# Charging.net
KiCad netlist of a schematic drawn in Altium Designer
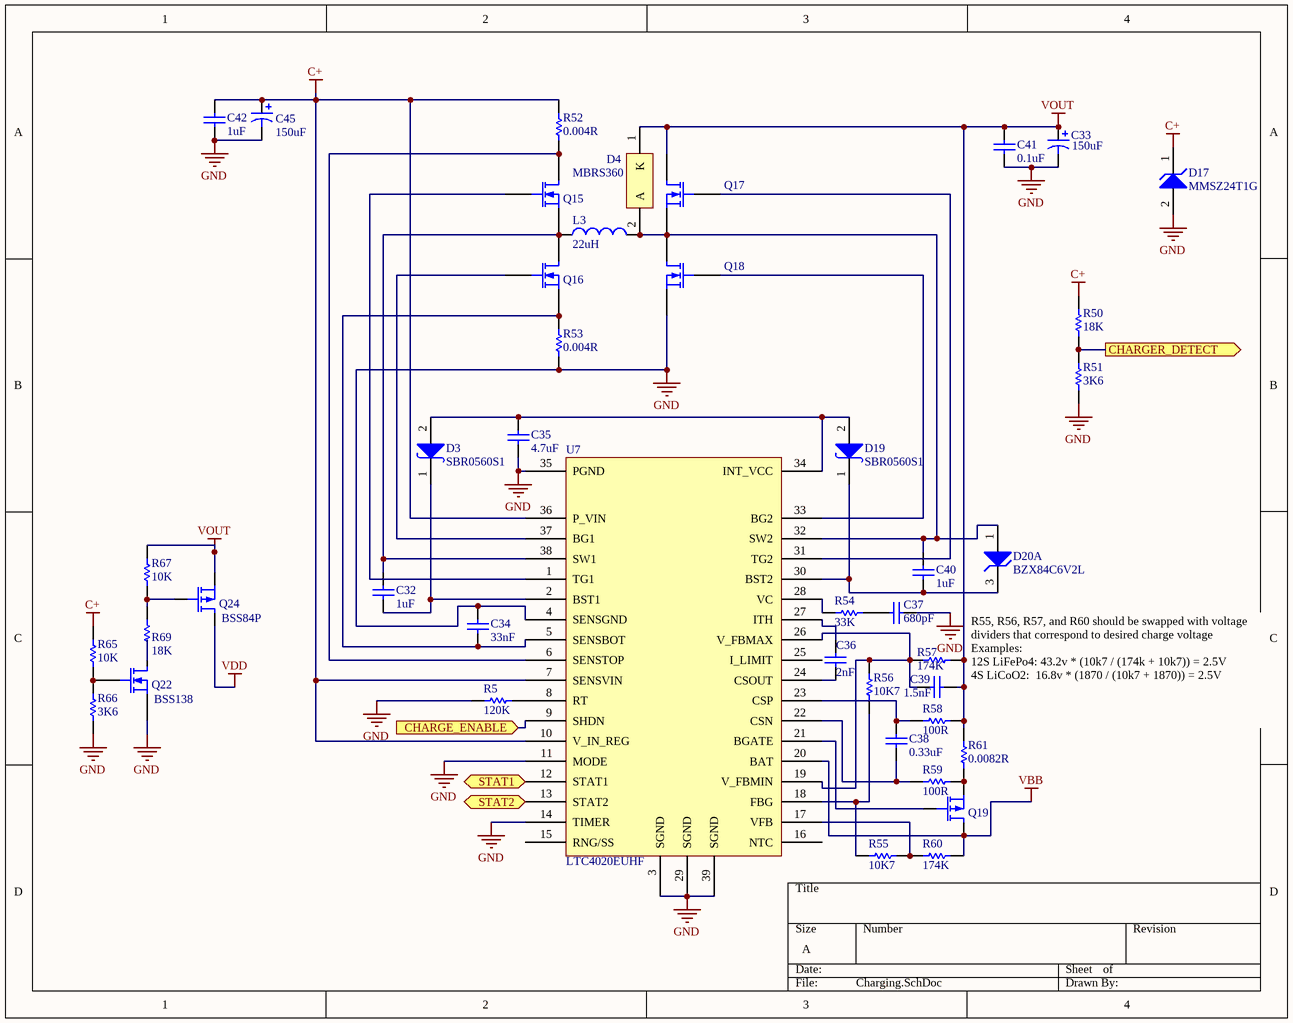
[diagram p0: Charging.SchDoc]

(export (version "E")
  (design (tool "Eeschema 10.0.6"))
  (components
    (comp (ref "C32")
      (value "1uF")
      (footprint "CAPC0603(1608)100_L")
      (description "CAP 1uF 25V Â±10% 0603 (1608 Metric) Thickness 1mm SMD")
      (fields (field (name "TOLERANCE") "Â±10%"))
      (libsource (lib "Altium Content Vault") (part "CAP"))
    )
    (comp (ref "C33")
      (value "150uF")
      (footprint "CAP 180uF 50V")
      (description "Polarized Capacitor (Axial)")
      (fields (field (name "PUBLISHER") "Altium Limited"))
      (libsource (lib "Components") (part "CAP 180uF 50V"))
    )
    (comp (ref "C34")
      (value "33nF")
      (footprint "CAPC0603(1608)100_L")
      (description "CAP 33nF 25V Â±5% 0603 (1608 Metric) Thickness 1mm SMD")
      (fields (field (name "TOLERANCE") "Â±5%"))
      (libsource (lib "Altium Content Vault") (part "CMP-1035-02463-1"))
    )
    (comp (ref "C35")
      (value "4.7uF")
      (footprint "CAPC0603(1608)55_L")
      (description "CAP 4.7uF 6.3V Â±10% 0603 (1608 Metric) Thickness 0.55mm SMD")
      (fields (field (name "TOLERANCE") "Â±10%"))
      (libsource (lib "Altium Content Vault") (part "CMP-1035-02779-1"))
    )
    (comp (ref "C36")
      (value "2nF")
      (footprint "CAPC0603(1608)100_L")
      (description "CAP 2.2nF 6.3V Â±5% 0603 (1608 Metric) Thickness 1mm SMD")
      (fields (field (name "TOLERANCE") "Â±5%"))
      (libsource (lib "Altium Content Vault") (part "CAP"))
    )
    (comp (ref "C37")
      (value "680pF")
      (footprint "CAPC0603(1608)100_L")
      (description "CAP 680pF 6.3V Â±5% 0603 (1608 Metric) Thickness 1mm SMD")
      (fields (field (name "TOLERANCE") "Â±5%"))
      (libsource (lib "Altium Content Vault") (part "CAP"))
    )
    (comp (ref "C38")
      (value "0.33uF")
      (footprint "CAPC0603(1608)100_L")
      (description "CAP 330nF 50V Â±10% 0603 (1608 Metric) Thickness 1mm SMD")
      (fields (field (name "TOLERANCE") "Â±10%"))
      (libsource (lib "Altium Content Vault") (part "CMP-1035-02679-1"))
    )
    (comp (ref "C39")
      (value "1.5nF")
      (footprint "CAPC0603(1608)100_N")
      (description "CAP 1.5nF 6.3V Â±5% 0603 (1608 Metric) Thickness 1mm SMD")
      (fields (field (name "TOLERANCE") "Â±5%"))
      (libsource (lib "Altium Content Vault") (part "CAP"))
    )
    (comp (ref "C40")
      (value "1uF")
      (footprint "CAPC0603(1608)100_L")
      (description "CAP 1uF 25V Â±10% 0603 (1608 Metric) Thickness 1mm SMD")
      (fields (field (name "TOLERANCE") "Â±10%"))
      (libsource (lib "Altium Content Vault") (part "CAP"))
    )
    (comp (ref "C41")
      (value "0.1uF")
      (footprint "CAPC0603(1608)100_L")
      (description "CAP 100nF 50V Â±5% 0603 (1608 Metric) Thickness 1mm SMD")
      (fields (field (name "TOLERANCE") "Â±5%"))
      (libsource (lib "Altium Content Vault") (part "CMP-1035-02591-1"))
    )
    (comp (ref "C42")
      (value "1uF")
      (footprint "CAPC0603(1608)100_L")
      (description "CAP 1uF 25V Â±10% 0603 (1608 Metric) Thickness 1mm SMD")
      (fields (field (name "TOLERANCE") "Â±10%"))
      (libsource (lib "Altium Content Vault") (part "CAP"))
    )
    (comp (ref "C45")
      (value "150uF")
      (footprint "CAP 150uF 25V")
      (description "Polarized Capacitor (Axial)")
      (fields (field (name "PUBLISHER") "Altium Limited"))
      (libsource (lib "Components") (part "CAP 150uF 25V"))
    )
    (comp (ref "D3")
      (value "SBR0560S1")
      (footprint "SOD-123")
      (libsource (lib "Components") (part "SBR0560S1"))
    )
    (comp (ref "D4")
      (value "MBRS360")
      (footprint "ONSC-SMB-2-403A-03_H_V")
      (description "Schottky Power Rectifier, 2-Pin SMB, Pb-Free, Tape and Reel")
      (fields (field (name "MANUFACTURER") "On Semiconductor") (field (name "PARTNUMBER") "MBRS360BT3G"))
      (libsource (lib "Altium Content Vault") (part "ONSC-D-K1A2-2_A"))
    )
    (comp (ref "D17")
      (value "MMSZ24T1G")
      (footprint "ONSC-SOD-123-2-425-04_V")
      (description "Zener Voltage Regulator, 500 mW, 2-Pin SOD-123, Pb-Free, Tape and Reel")
      (fields (field (name "MANUFACTURER") "On Semiconductor"))
      (libsource (lib "Altium Content Vault") (part "CMP-1060-00237-1"))
    )
    (comp (ref "D19")
      (value "SBR0560S1")
      (footprint "SOD-123")
      (libsource (lib "Components") (part "SBR0560S1"))
    )
    (comp (ref "D20")
      (value "BZX84C6V2L")
      (footprint "ONSC-SOT-23-3-318-08_V")
      (description "Zener Voltage Regulator, 225 mW, 3-Pin SOT-23, Pb-Free, Tape and Reel")
      (fields (field (name "MANUFACTURER") "On Semiconductor") (field (name "PARTNUMBER") "BZX84C6V2LT3G"))
      (libsource (lib "Altium Content Vault") (part "CMP-1060-00911-1"))
    )
    (comp (ref "L3")
      (value "22uH")
      (footprint "IHLP-6767GZ")
      (description "Inductor")
      (fields (field (name "PUBLISHER") "Altium Limited"))
      (libsource (lib "Components") (part "IHLP6767"))
    )
    (comp (ref "Q15")
      (value "FDS5672")
      (footprint "SOIC127P600X175-8N")
      (description "N-Channel MOSFET")
      (fields (field (name "PUBLISHER") "Altium Limited"))
      (libsource (lib "Components") (part "MOSFET-N"))
    )
    (comp (ref "Q16")
      (value "FDS5672")
      (footprint "SOIC127P600X175-8N")
      (description "N-Channel MOSFET")
      (fields (field (name "PUBLISHER") "Altium Limited"))
      (libsource (lib "Components") (part "MOSFET-N"))
    )
    (comp (ref "Q17")
      (value "FDS5672")
      (footprint "SOIC127P600X175-8N")
      (description "N-Channel MOSFET")
      (fields (field (name "PUBLISHER") "Altium Limited"))
      (libsource (lib "Components") (part "MOSFET-N"))
    )
    (comp (ref "Q18")
      (value "FDS5672")
      (footprint "SOIC127P600X175-8N")
      (description "N-Channel MOSFET")
      (fields (field (name "PUBLISHER") "Altium Limited"))
      (libsource (lib "Components") (part "MOSFET-N"))
    )
    (comp (ref "Q19")
      (value "SQJ461EP-T1")
      (footprint "SOIC127P600X175-8N")
      (description "P-Channel MOSFET")
      (fields (field (name "PUBLISHER") "Altium Limited"))
      (libsource (lib "Components") (part "MOSFET-P"))
    )
    (comp (ref "Q22")
      (value "BSS138")
      (footprint "SOT23-3")
      (description "N-Channel MOSFET")
      (fields (field (name "PUBLISHER") "Altium Limited"))
      (libsource (lib "Components") (part "MOSFET-N"))
    )
    (comp (ref "Q24")
      (value "BSS84P")
      (footprint "SOT23-3")
      (description "P-Channel MOSFET")
      (fields (field (name "MODEL") "BSS84P") (field (name "PUBLISHER") "Altium Limited"))
      (libsource (lib "Components") (part "MOSFET-P"))
    )
    (comp (ref "R5")
      (value "120K")
      (footprint "RESC0603(1608)_L")
      (description "120K 0.1W 5% 0603 (1608 Metric)  SMD")
      (fields (field (name "POWER") "0.1 W") (field (name "TOLERANCE") "5 %"))
      (libsource (lib "Altium Content Vault") (part "CMP-1012-00124-1"))
    )
    (comp (ref "R50")
      (value "18K")
      (footprint "RESC0603(1608)_L")
      (description "18K 0.1W 1% 0603 (1608 Metric)  SMD")
      (fields (field (name "POWER") "0.1 W") (field (name "TOLERANCE") "1 %"))
      (libsource (lib "Altium Content Vault") (part "CMP-1012-00650-1"))
    )
    (comp (ref "R51")
      (value "3K6")
      (footprint "RESC0603(1608)_L")
      (description "3K6 0.1W 1% 0603 (1608 Metric)  SMD")
      (fields (field (name "TOLERANCE") "1 %") (field (name "POWER") "0.1 W"))
      (libsource (lib "Altium Content Vault") (part "RES"))
    )
    (comp (ref "R52")
      (value "0.004R")
      (footprint "RESC1206(3216)_L")
      (description "1R 0.25W 1% 1206 (3216 Metric)  SMD")
      (fields (field (name "POWER") "0.25 W") (field (name "TOLERANCE") "1 %"))
      (libsource (lib "Altium Content Vault") (part "RES"))
    )
    (comp (ref "R53")
      (value "0.004R")
      (footprint "RESC1206(3216)_L")
      (description "1R 0.25W 1% 1206 (3216 Metric)  SMD")
      (fields (field (name "POWER") "0.25 W") (field (name "TOLERANCE") "1 %"))
      (libsource (lib "Altium Content Vault") (part "RES"))
    )
    (comp (ref "R54")
      (value "33K")
      (footprint "RESC0603(1608)_N")
      (description "33K 0.1W 1% 0603 (1608 Metric)  SMD")
      (fields (field (name "TOLERANCE") "1 %") (field (name "POWER") "0.1 W"))
      (libsource (lib "Altium Content Vault") (part "RES"))
    )
    (comp (ref "R55")
      (value "10K7")
      (footprint "RESC0603(1608)_L")
      (description "110K 0.1W 5% 0603 (1608 Metric)  SMD")
      (fields (field (name "TOLERANCE") "5 %") (field (name "POWER") "0.1 W"))
      (libsource (lib "Altium Content Vault") (part "CMP-1012-00123-1"))
    )
    (comp (ref "R56")
      (value "10K7")
      (footprint "RESC0603(1608)_L")
      (description "110K 0.1W 5% 0603 (1608 Metric)  SMD")
      (fields (field (name "TOLERANCE") "5 %") (field (name "POWER") "0.1 W"))
      (libsource (lib "Altium Content Vault") (part "CMP-1012-00123-1"))
    )
    (comp (ref "R57")
      (value "174K")
      (footprint "RESC0603(1608)_L")
      (description "1M8 0.1W 5% 0603 (1608 Metric)  SMD")
      (fields (field (name "TOLERANCE") "5 %") (field (name "POWER") "0.1 W"))
      (libsource (lib "Altium Content Vault") (part "RES"))
    )
    (comp (ref "R58")
      (value "100R")
      (footprint "RESC0603(1608)_L")
      (description "100R 0.1W 5% 0603 (1608 Metric)  SMD")
      (fields (field (name "TOLERANCE") "5 %") (field (name "POWER") "0.1 W"))
      (libsource (lib "Altium Content Vault") (part "RES"))
    )
    (comp (ref "R59")
      (value "100R")
      (footprint "RESC0603(1608)_L")
      (description "100R 0.1W 5% 0603 (1608 Metric)  SMD")
      (fields (field (name "TOLERANCE") "5 %") (field (name "POWER") "0.1 W"))
      (libsource (lib "Altium Content Vault") (part "RES"))
    )
    (comp (ref "R60")
      (value "174K")
      (footprint "RESC0603(1608)_L")
      (description "1M8 0.1W 5% 0603 (1608 Metric)  SMD")
      (fields (field (name "TOLERANCE") "5 %") (field (name "POWER") "0.1 W"))
      (libsource (lib "Altium Content Vault") (part "CMP-1012-00152-1"))
    )
    (comp (ref "R61")
      (value "0.0082R")
      (footprint "RESC2010(5025)_M")
      (description "1R 0.75W 1% 2010 (5025 Metric)  SMD")
      (fields (field (name "TOLERANCE") "1 %") (field (name "POWER") "0.75 W"))
      (libsource (lib "Altium Content Vault") (part "CMP-1017-00171-1"))
    )
    (comp (ref "R65")
      (value "10K")
      (footprint "RESC0603(1608)_N")
      (description "10K 0.1W 5% 0603 (1608 Metric)  SMD")
      (fields (field (name "TOLERANCE") "5 %") (field (name "POWER") "0.1 W"))
      (libsource (lib "Altium Content Vault") (part "RES"))
    )
    (comp (ref "R66")
      (value "3K6")
      (footprint "RESC0603(1608)_N")
      (description "3K6 0.1W 5% 0603 (1608 Metric)  SMD")
      (fields (field (name "POWER") "0.1 W") (field (name "TOLERANCE") "5 %"))
      (libsource (lib "Altium Content Vault") (part "RES"))
    )
    (comp (ref "R67")
      (value "10K")
      (footprint "RESC0603(1608)_N")
      (description "10K 0.1W 5% 0603 (1608 Metric)  SMD")
      (fields (field (name "TOLERANCE") "5 %") (field (name "POWER") "0.1 W"))
      (libsource (lib "Altium Content Vault") (part "RES"))
    )
    (comp (ref "R69")
      (value "18K")
      (footprint "RESC0603(1608)_N")
      (description "18K 0.1W 5% 0603 (1608 Metric)  SMD")
      (fields (field (name "TOLERANCE") "5 %") (field (name "POWER") "0.1 W"))
      (libsource (lib "Altium Content Vault") (part "RES"))
    )
    (comp (ref "U7")
      (value "LTC4020EUHF")
      (footprint "QFN38")
      (libsource (lib "Components") (part "LTC4020EUHF"))
    )
  )
  (nets
    (net (code "1") (name "/CHARGER_DETECT") (class "Default")
      (node (ref "R50") (pin "1") (pinfunction "1_1") (pintype "passive"))
      (node (ref "R51") (pin "2") (pinfunction "2_2") (pintype "passive"))
    )
    (net (code "2") (name "/CHARGE_ENABLE") (class "Default")
      (node (ref "U7") (pin "9") (pinfunction "SHDN_9") (pintype "passive"))
    )
    (net (code "3") (name "/STAT1") (class "Default")
      (node (ref "U7") (pin "12") (pinfunction "STAT1_12") (pintype "passive"))
    )
    (net (code "4") (name "/STAT2") (class "Default")
      (node (ref "U7") (pin "13") (pinfunction "STAT2_13") (pintype "passive"))
    )
    (net (code "5") (name "C+") (class "Default")
      (node (ref "C42") (pin "2") (pinfunction "2_2") (pintype "passive"))
      (node (ref "C45") (pin "1") (pinfunction "1_1") (pintype "passive"))
      (node (ref "D17") (pin "1") (pinfunction "K_1") (pintype "passive"))
      (node (ref "R50") (pin "2") (pinfunction "2_2") (pintype "passive"))
      (node (ref "R52") (pin "2") (pinfunction "2_2") (pintype "passive"))
      (node (ref "R65") (pin "2") (pinfunction "2_2") (pintype "passive"))
      (node (ref "U7") (pin "10") (pinfunction "V_IN_REG_10") (pintype "passive"))
      (node (ref "U7") (pin "36") (pinfunction "P_VIN_36") (pintype "passive"))
      (node (ref "U7") (pin "7") (pinfunction "SENSVIN_7") (pintype "passive"))
    )
    (net (code "6") (name "GND") (class "Default")
      (node (ref "C33") (pin "2") (pinfunction "2_2") (pintype "passive"))
      (node (ref "C34") (pin "2") (pinfunction "2_2") (pintype "passive"))
      (node (ref "C35") (pin "1") (pinfunction "1_1") (pintype "passive"))
      (node (ref "C37") (pin "2") (pinfunction "2_2") (pintype "passive"))
      (node (ref "C41") (pin "1") (pinfunction "1_1") (pintype "passive"))
      (node (ref "C42") (pin "1") (pinfunction "1_1") (pintype "passive"))
      (node (ref "C45") (pin "2") (pinfunction "2_2") (pintype "passive"))
      (node (ref "D17") (pin "2") (pinfunction "A_2") (pintype "passive"))
      (node (ref "Q18") (pin "3") (pinfunction "S_3") (pintype "passive"))
      (node (ref "Q22") (pin "3") (pinfunction "S_3") (pintype "passive"))
      (node (ref "R5") (pin "2") (pinfunction "2_2") (pintype "passive"))
      (node (ref "R51") (pin "1") (pinfunction "1_1") (pintype "passive"))
      (node (ref "R53") (pin "1") (pinfunction "1_1") (pintype "passive"))
      (node (ref "R66") (pin "1") (pinfunction "1_1") (pintype "passive"))
      (node (ref "U7") (pin "11") (pinfunction "MODE_11") (pintype "passive"))
      (node (ref "U7") (pin "14") (pinfunction "TIMER_14") (pintype "passive"))
      (node (ref "U7") (pin "29") (pinfunction "SGND_29") (pintype "passive"))
      (node (ref "U7") (pin "3") (pinfunction "SGND_3") (pintype "passive"))
      (node (ref "U7") (pin "35") (pinfunction "PGND_35") (pintype "passive"))
      (node (ref "U7") (pin "39") (pinfunction "SGND_39") (pintype "passive"))
      (node (ref "U7") (pin "4") (pinfunction "SENSGND_4") (pintype "passive"))
    )
    (net (code "7") (name "Net-(C37-Pad1)") (class "Default")
      (node (ref "C37") (pin "1") (pinfunction "1_1") (pintype "passive"))
      (node (ref "R54") (pin "2") (pinfunction "2_2") (pintype "passive"))
    )
    (net (code "8") (name "Net-(D3-K)") (class "Default")
      (node (ref "C32") (pin "1") (pinfunction "1_1") (pintype "passive"))
      (node (ref "D3") (pin "1") (pinfunction "K_1") (pintype "passive"))
      (node (ref "U7") (pin "2") (pinfunction "BST1_2") (pintype "passive"))
    )
    (net (code "9") (name "Net-(D19-A)") (class "Default")
      (node (ref "C35") (pin "2") (pinfunction "2_2") (pintype "passive"))
      (node (ref "D19") (pin "2") (pinfunction "A_2") (pintype "passive"))
      (node (ref "D3") (pin "2") (pinfunction "A_2") (pintype "passive"))
      (node (ref "U7") (pin "34") (pinfunction "INT_VCC_34") (pintype "passive"))
    )
    (net (code "10") (name "Net-(D19-K)") (class "Default")
      (node (ref "C40") (pin "1") (pinfunction "1_1") (pintype "passive"))
      (node (ref "D19") (pin "1") (pinfunction "K_1") (pintype "passive"))
      (node (ref "D20") (pin "3") (pinfunction "K_3") (pintype "passive"))
      (node (ref "U7") (pin "30") (pinfunction "BST2_30") (pintype "passive"))
    )
    (net (code "11") (name "Net-(D20A-A)") (class "Default")
      (node (ref "C40") (pin "2") (pinfunction "2_2") (pintype "passive"))
      (node (ref "D20") (pin "1") (pinfunction "A_1") (pintype "passive"))
      (node (ref "D4") (pin "2") (pinfunction "A_2") (pintype "passive"))
      (node (ref "L3") (pin "2") (pinfunction "2_2") (pintype "passive"))
      (node (ref "Q17") (pin "3") (pinfunction "S_3") (pintype "passive"))
      (node (ref "Q18") (pin "2") (pinfunction "D_2") (pintype "passive"))
      (node (ref "U7") (pin "32") (pinfunction "SW2_32") (pintype "passive"))
    )
    (net (code "12") (name "Net-(Q15-D)") (class "Default")
      (node (ref "Q15") (pin "2") (pinfunction "D_2") (pintype "passive"))
      (node (ref "R52") (pin "1") (pinfunction "1_1") (pintype "passive"))
      (node (ref "U7") (pin "6") (pinfunction "SENSTOP_6") (pintype "passive"))
    )
    (net (code "13") (name "Net-(Q15-G)") (class "Default")
      (node (ref "Q15") (pin "1") (pinfunction "G_1") (pintype "passive"))
      (node (ref "U7") (pin "1") (pinfunction "TG1_1") (pintype "passive"))
    )
    (net (code "14") (name "Net-(Q15-S)") (class "Default")
      (node (ref "C32") (pin "2") (pinfunction "2_2") (pintype "passive"))
      (node (ref "L3") (pin "1") (pinfunction "1_1") (pintype "passive"))
      (node (ref "Q15") (pin "3") (pinfunction "S_3") (pintype "passive"))
      (node (ref "Q16") (pin "2") (pinfunction "D_2") (pintype "passive"))
      (node (ref "U7") (pin "38") (pinfunction "SW1_38") (pintype "passive"))
    )
    (net (code "15") (name "Net-(Q16-G)") (class "Default")
      (node (ref "Q16") (pin "1") (pinfunction "G_1") (pintype "passive"))
      (node (ref "U7") (pin "37") (pinfunction "BG1_37") (pintype "passive"))
    )
    (net (code "16") (name "Net-(Q16-S)") (class "Default")
      (node (ref "C34") (pin "1") (pinfunction "1_1") (pintype "passive"))
      (node (ref "Q16") (pin "3") (pinfunction "S_3") (pintype "passive"))
      (node (ref "R53") (pin "2") (pinfunction "2_2") (pintype "passive"))
      (node (ref "U7") (pin "5") (pinfunction "SENSBOT_5") (pintype "passive"))
    )
    (net (code "17") (name "Net-(Q17-G)") (class "Default")
      (node (ref "Q17") (pin "1") (pinfunction "G_1") (pintype "passive"))
      (node (ref "U7") (pin "31") (pinfunction "TG2_31") (pintype "passive"))
    )
    (net (code "18") (name "Net-(Q18-G)") (class "Default")
      (node (ref "Q18") (pin "1") (pinfunction "G_1") (pintype "passive"))
      (node (ref "U7") (pin "33") (pinfunction "BG2_33") (pintype "passive"))
    )
    (net (code "19") (name "Net-(Q19-G)") (class "Default")
      (node (ref "Q19") (pin "1") (pinfunction "G_1") (pintype "passive"))
      (node (ref "U7") (pin "21") (pinfunction "BGATE_21") (pintype "passive"))
    )
    (net (code "20") (name "Net-(Q19-S)") (class "Default")
      (node (ref "Q19") (pin "3") (pinfunction "S_3") (pintype "passive"))
      (node (ref "R59") (pin "2") (pinfunction "2_2") (pintype "passive"))
      (node (ref "R61") (pin "1") (pinfunction "1_1") (pintype "passive"))
    )
    (net (code "21") (name "Net-(Q22-D)") (class "Default")
      (node (ref "Q22") (pin "2") (pinfunction "D_2") (pintype "passive"))
      (node (ref "R69") (pin "1") (pinfunction "1_1") (pintype "passive"))
    )
    (net (code "22") (name "Net-(Q22-G)") (class "Default")
      (node (ref "Q22") (pin "1") (pinfunction "G_1") (pintype "passive"))
      (node (ref "R65") (pin "1") (pinfunction "1_1") (pintype "passive"))
      (node (ref "R66") (pin "2") (pinfunction "2_2") (pintype "passive"))
    )
    (net (code "23") (name "Net-(Q24-G)") (class "Default")
      (node (ref "Q24") (pin "1") (pinfunction "G_1") (pintype "passive"))
      (node (ref "R67") (pin "1") (pinfunction "1_1") (pintype "passive"))
      (node (ref "R69") (pin "2") (pinfunction "2_2") (pintype "passive"))
    )
    (net (code "24") (name "Net-(U7-CSN)") (class "Default")
      (node (ref "C38") (pin "1") (pinfunction "1_1") (pintype "passive"))
      (node (ref "R59") (pin "1") (pinfunction "1_1") (pintype "passive"))
      (node (ref "U7") (pin "22") (pinfunction "CSN_22") (pintype "passive"))
    )
    (net (code "25") (name "Net-(U7-CSOUT)") (class "Default")
      (node (ref "C36") (pin "1") (pinfunction "1_1") (pintype "passive"))
      (node (ref "U7") (pin "24") (pinfunction "CSOUT_24") (pintype "passive"))
    )
    (net (code "26") (name "Net-(U7-CSP)") (class "Default")
      (node (ref "C38") (pin "2") (pinfunction "2_2") (pintype "passive"))
      (node (ref "R58") (pin "1") (pinfunction "1_1") (pintype "passive"))
      (node (ref "U7") (pin "23") (pinfunction "CSP_23") (pintype "passive"))
    )
    (net (code "27") (name "Net-(U7-FBG)") (class "Default")
      (node (ref "R55") (pin "1") (pinfunction "1_1") (pintype "passive"))
      (node (ref "R56") (pin "1") (pinfunction "1_1") (pintype "passive"))
      (node (ref "U7") (pin "18") (pinfunction "FBG_18") (pintype "passive"))
    )
    (net (code "28") (name "Net-(U7-ITH)") (class "Default")
      (node (ref "C36") (pin "2") (pinfunction "2_2") (pintype "passive"))
      (node (ref "U7") (pin "27") (pinfunction "ITH_27") (pintype "passive"))
    )
    (net (code "29") (name "Net-(U7-RT)") (class "Default")
      (node (ref "R5") (pin "1") (pinfunction "1_1") (pintype "passive"))
      (node (ref "U7") (pin "8") (pinfunction "RT_8") (pintype "passive"))
    )
    (net (code "30") (name "Net-(U7-VC)") (class "Default")
      (node (ref "R54") (pin "1") (pinfunction "1_1") (pintype "passive"))
      (node (ref "U7") (pin "28") (pinfunction "VC_28") (pintype "passive"))
    )
    (net (code "31") (name "Net-(U7-VFB)") (class "Default")
      (node (ref "R55") (pin "2") (pinfunction "2_2") (pintype "passive"))
      (node (ref "R60") (pin "1") (pinfunction "1_1") (pintype "passive"))
      (node (ref "U7") (pin "17") (pinfunction "VFB_17") (pintype "passive"))
    )
    (net (code "32") (name "Net-(U7-V_FBMAX)") (class "Default")
      (node (ref "C39") (pin "1") (pinfunction "1_1") (pintype "passive"))
      (node (ref "R56") (pin "2") (pinfunction "2_2") (pintype "passive"))
      (node (ref "R57") (pin "1") (pinfunction "1_1") (pintype "passive"))
      (node (ref "U7") (pin "19") (pinfunction "V_FBMIN_19") (pintype "passive"))
      (node (ref "U7") (pin "26") (pinfunction "V_FBMAX_26") (pintype "passive"))
    )
    (net (code "33") (name "VBB") (class "Default")
      (node (ref "Q19") (pin "2") (pinfunction "D_2") (pintype "passive"))
      (node (ref "R60") (pin "2") (pinfunction "2_2") (pintype "passive"))
      (node (ref "U7") (pin "20") (pinfunction "BAT_20") (pintype "passive"))
    )
    (net (code "34") (name "VDD") (class "Default")
      (node (ref "Q24") (pin "2") (pinfunction "D_2") (pintype "passive"))
    )
    (net (code "35") (name "VOUT") (class "Default")
      (node (ref "C33") (pin "1") (pinfunction "1_1") (pintype "passive"))
      (node (ref "C39") (pin "2") (pinfunction "2_2") (pintype "passive"))
      (node (ref "C41") (pin "2") (pinfunction "2_2") (pintype "passive"))
      (node (ref "D4") (pin "1") (pinfunction "K_1") (pintype "passive"))
      (node (ref "Q17") (pin "2") (pinfunction "D_2") (pintype "passive"))
      (node (ref "Q24") (pin "3") (pinfunction "S_3") (pintype "passive"))
      (node (ref "R57") (pin "2") (pinfunction "2_2") (pintype "passive"))
      (node (ref "R58") (pin "2") (pinfunction "2_2") (pintype "passive"))
      (node (ref "R61") (pin "2") (pinfunction "2_2") (pintype "passive"))
      (node (ref "R67") (pin "2") (pinfunction "2_2") (pintype "passive"))
    )
    (net (code "36") (name "unconnected-(U7-I_LIMIT-Pad25)") (class "Default")
      (node (ref "U7") (pin "25") (pinfunction "I_LIMIT_25") (pintype "passive"))
    )
    (net (code "37") (name "unconnected-(U7-NTC-Pad16)") (class "Default")
      (node (ref "U7") (pin "16") (pinfunction "NTC_16") (pintype "passive"))
    )
    (net (code "38") (name "unconnected-(U7-RNG{slash}SS-Pad15)") (class "Default")
      (node (ref "U7") (pin "15") (pinfunction "RNG/SS_15") (pintype "passive"))
    )
  )
)
